# 8x8BulbMatrix.net
KiCad netlist of a schematic drawn in EAGLE
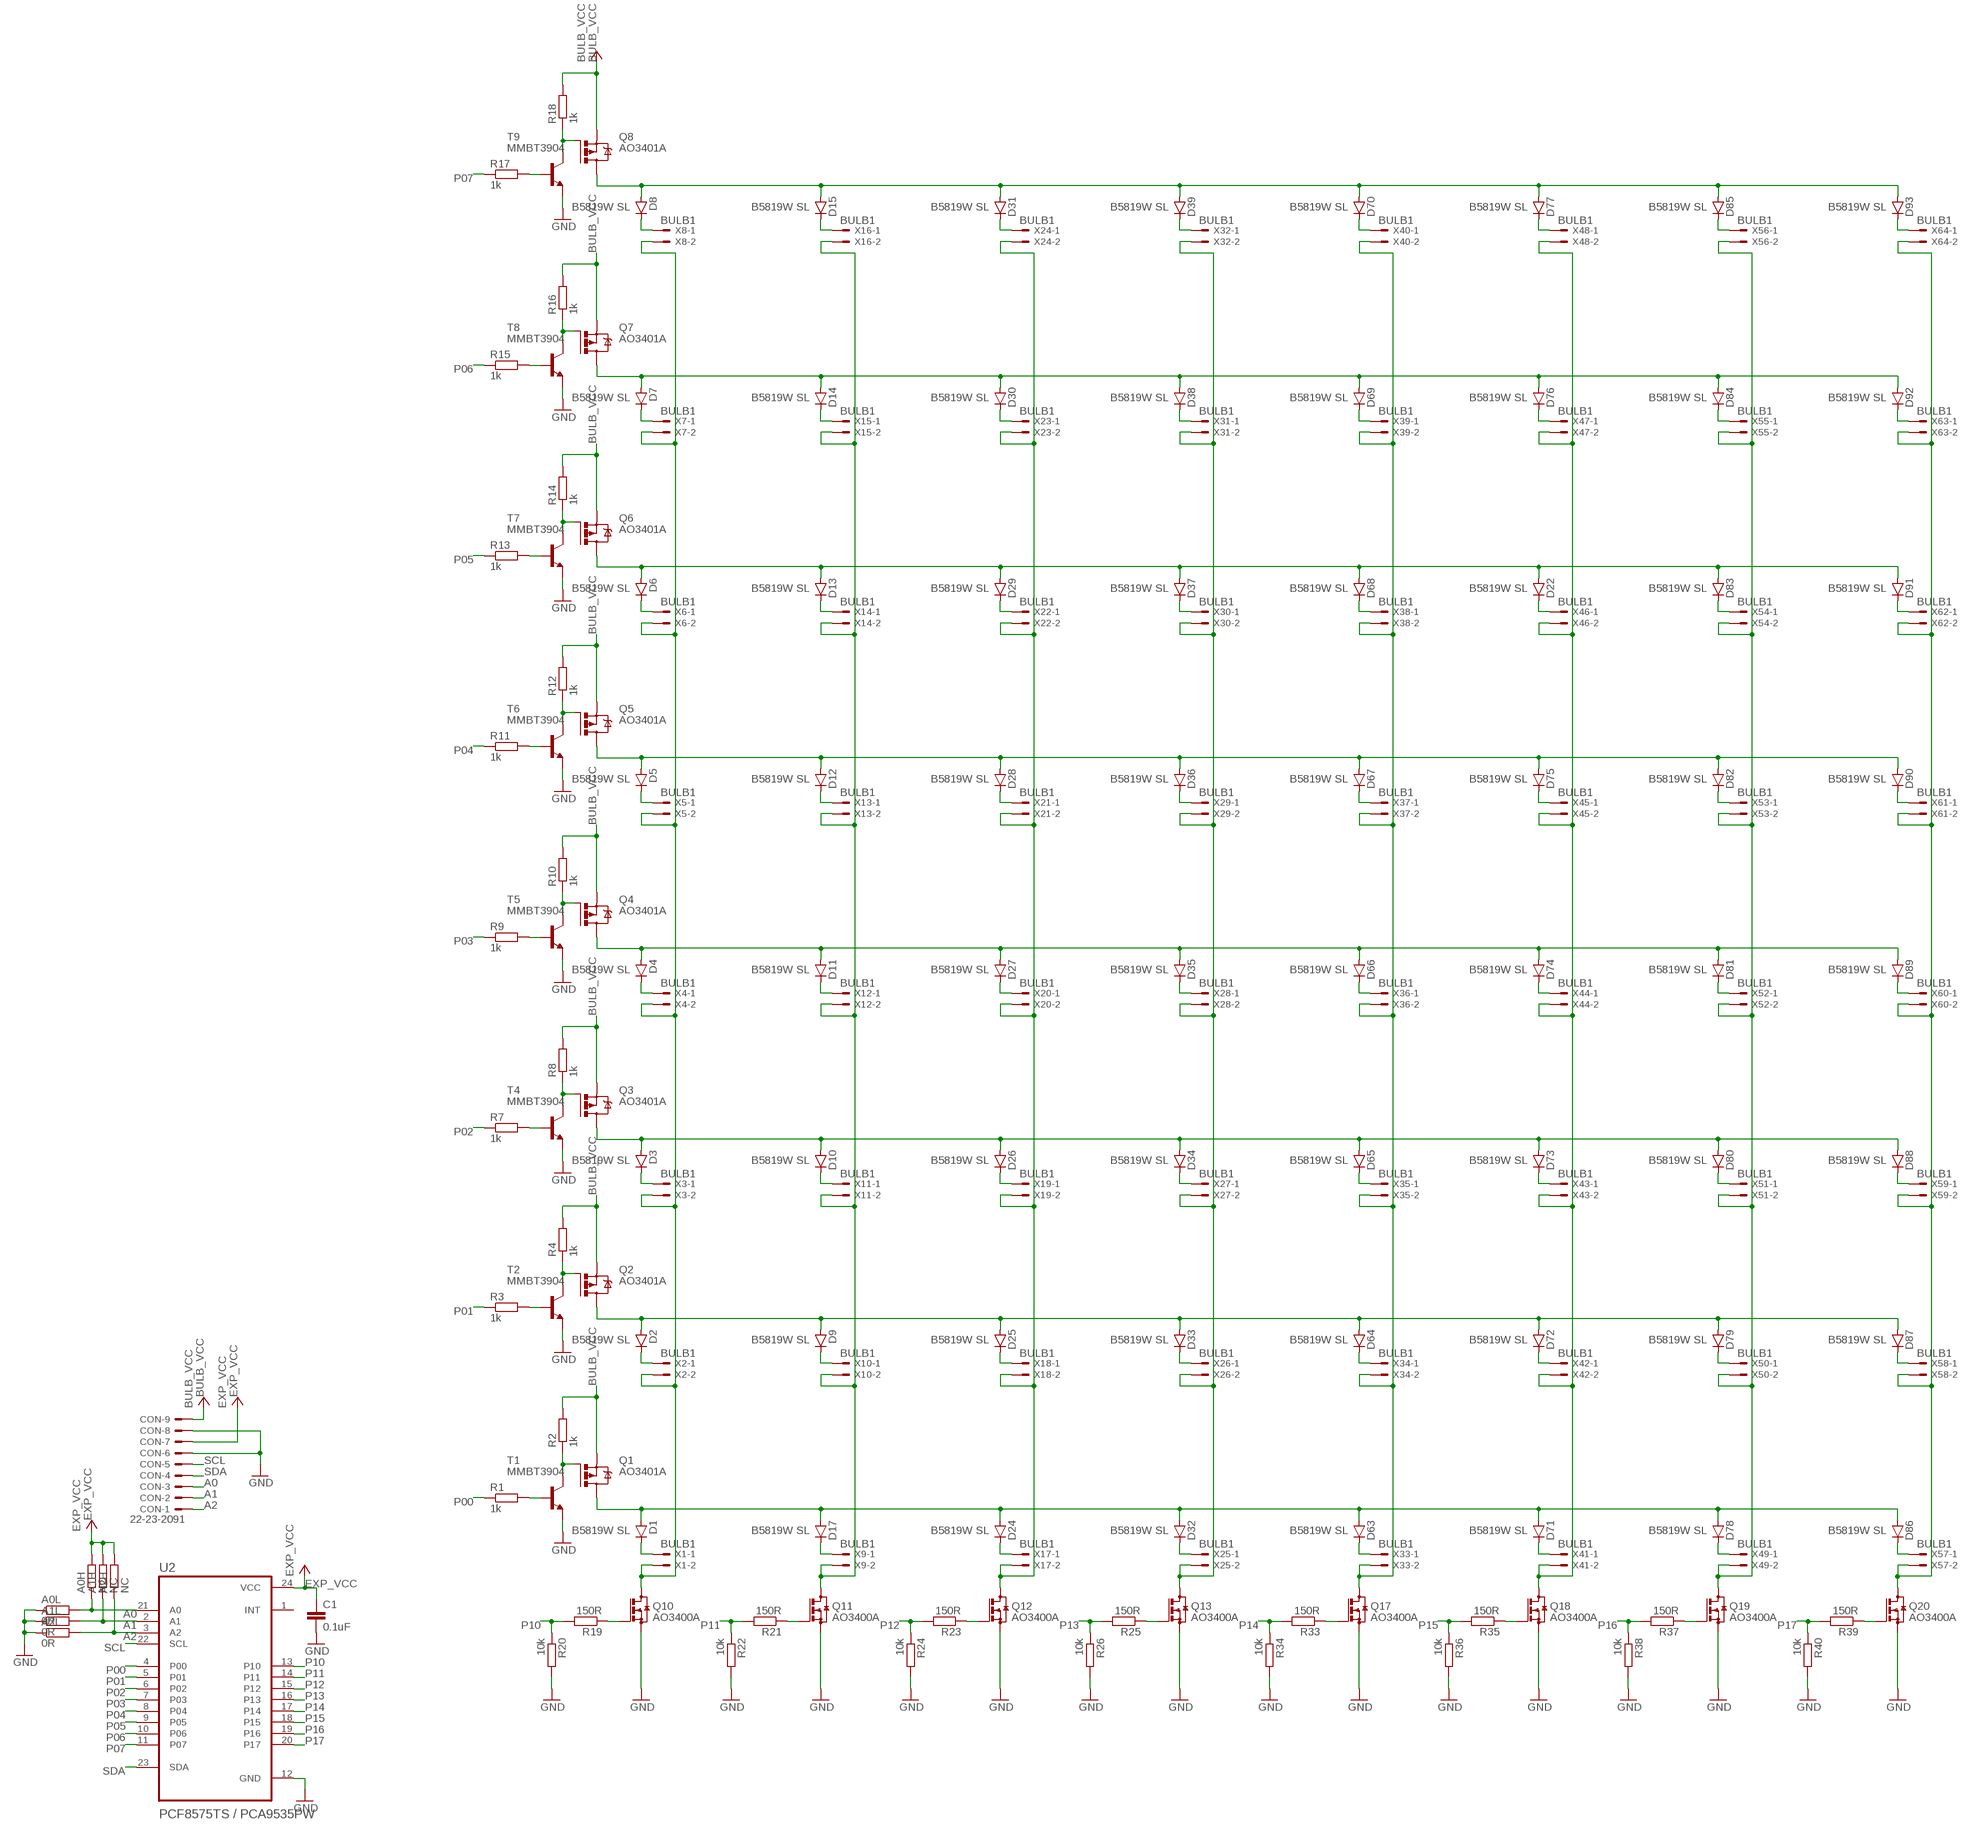
[diagram p0: schematic, sheet 1]

(export (version "E")
  (design (tool "Eeschema 10.0.6"))
  (components
    (comp (ref "A0H")
      (value "NC")
      (footprint "eagle-import:R0603")
      (libsource (lib "eagle-import") (part "R-EU_R0603"))
    )
    (comp (ref "A0L")
      (value "0R")
      (footprint "eagle-import:R0603")
      (libsource (lib "eagle-import") (part "R-EU_R0603"))
    )
    (comp (ref "A1H")
      (value "NC")
      (footprint "eagle-import:R0603")
      (libsource (lib "eagle-import") (part "R-EU_R0603"))
    )
    (comp (ref "A1L")
      (value "0R")
      (footprint "eagle-import:R0603")
      (libsource (lib "eagle-import") (part "R-EU_R0603"))
    )
    (comp (ref "A2H")
      (value "NC")
      (footprint "eagle-import:R0603")
      (libsource (lib "eagle-import") (part "R-EU_R0603"))
    )
    (comp (ref "A2L")
      (value "0R")
      (footprint "eagle-import:R0603")
      (libsource (lib "eagle-import") (part "R-EU_R0603"))
    )
    (comp (ref "C1")
      (value "0.1uF")
      (footprint "eagle-import:C0805")
      (libsource (lib "eagle-import") (part "C-EUC0805"))
    )
    (comp (ref "CON")
      (value "22-23-2091")
      (footprint "eagle-import:22-23-2091")
      (fields (field (name "MF") "MOLEX"))
      (libsource (lib "eagle-import") (part "22-23-2091"))
    )
    (comp (ref "D1")
      (value "B5819W SL")
      (footprint "eagle-import:SOD123")
      (libsource (lib "eagle-import") (part "D-SOD123"))
    )
    (comp (ref "D2")
      (value "B5819W SL")
      (footprint "eagle-import:SOD123")
      (libsource (lib "eagle-import") (part "D-SOD123"))
    )
    (comp (ref "D3")
      (value "B5819W SL")
      (footprint "eagle-import:SOD123")
      (libsource (lib "eagle-import") (part "D-SOD123"))
    )
    (comp (ref "D4")
      (value "B5819W SL")
      (footprint "eagle-import:SOD123")
      (libsource (lib "eagle-import") (part "D-SOD123"))
    )
    (comp (ref "D5")
      (value "B5819W SL")
      (footprint "eagle-import:SOD123")
      (libsource (lib "eagle-import") (part "D-SOD123"))
    )
    (comp (ref "D6")
      (value "B5819W SL")
      (footprint "eagle-import:SOD123")
      (libsource (lib "eagle-import") (part "D-SOD123"))
    )
    (comp (ref "D7")
      (value "B5819W SL")
      (footprint "eagle-import:SOD123")
      (libsource (lib "eagle-import") (part "D-SOD123"))
    )
    (comp (ref "D8")
      (value "B5819W SL")
      (footprint "eagle-import:SOD123")
      (libsource (lib "eagle-import") (part "D-SOD123"))
    )
    (comp (ref "D9")
      (value "B5819W SL")
      (footprint "eagle-import:SOD123")
      (libsource (lib "eagle-import") (part "D-SOD123"))
    )
    (comp (ref "D10")
      (value "B5819W SL")
      (footprint "eagle-import:SOD123")
      (libsource (lib "eagle-import") (part "D-SOD123"))
    )
    (comp (ref "D11")
      (value "B5819W SL")
      (footprint "eagle-import:SOD123")
      (libsource (lib "eagle-import") (part "D-SOD123"))
    )
    (comp (ref "D12")
      (value "B5819W SL")
      (footprint "eagle-import:SOD123")
      (libsource (lib "eagle-import") (part "D-SOD123"))
    )
    (comp (ref "D13")
      (value "B5819W SL")
      (footprint "eagle-import:SOD123")
      (libsource (lib "eagle-import") (part "D-SOD123"))
    )
    (comp (ref "D14")
      (value "B5819W SL")
      (footprint "eagle-import:SOD123")
      (libsource (lib "eagle-import") (part "D-SOD123"))
    )
    (comp (ref "D15")
      (value "B5819W SL")
      (footprint "eagle-import:SOD123")
      (libsource (lib "eagle-import") (part "D-SOD123"))
    )
    (comp (ref "D17")
      (value "B5819W SL")
      (footprint "eagle-import:SOD123")
      (libsource (lib "eagle-import") (part "D-SOD123"))
    )
    (comp (ref "D22")
      (value "B5819W SL")
      (footprint "eagle-import:SOD123")
      (libsource (lib "eagle-import") (part "D-SOD123"))
    )
    (comp (ref "D24")
      (value "B5819W SL")
      (footprint "eagle-import:SOD123")
      (libsource (lib "eagle-import") (part "D-SOD123"))
    )
    (comp (ref "D25")
      (value "B5819W SL")
      (footprint "eagle-import:SOD123")
      (libsource (lib "eagle-import") (part "D-SOD123"))
    )
    (comp (ref "D26")
      (value "B5819W SL")
      (footprint "eagle-import:SOD123")
      (libsource (lib "eagle-import") (part "D-SOD123"))
    )
    (comp (ref "D27")
      (value "B5819W SL")
      (footprint "eagle-import:SOD123")
      (libsource (lib "eagle-import") (part "D-SOD123"))
    )
    (comp (ref "D28")
      (value "B5819W SL")
      (footprint "eagle-import:SOD123")
      (libsource (lib "eagle-import") (part "D-SOD123"))
    )
    (comp (ref "D29")
      (value "B5819W SL")
      (footprint "eagle-import:SOD123")
      (libsource (lib "eagle-import") (part "D-SOD123"))
    )
    (comp (ref "D30")
      (value "B5819W SL")
      (footprint "eagle-import:SOD123")
      (libsource (lib "eagle-import") (part "D-SOD123"))
    )
    (comp (ref "D31")
      (value "B5819W SL")
      (footprint "eagle-import:SOD123")
      (libsource (lib "eagle-import") (part "D-SOD123"))
    )
    (comp (ref "D32")
      (value "B5819W SL")
      (footprint "eagle-import:SOD123")
      (libsource (lib "eagle-import") (part "D-SOD123"))
    )
    (comp (ref "D33")
      (value "B5819W SL")
      (footprint "eagle-import:SOD123")
      (libsource (lib "eagle-import") (part "D-SOD123"))
    )
    (comp (ref "D34")
      (value "B5819W SL")
      (footprint "eagle-import:SOD123")
      (libsource (lib "eagle-import") (part "D-SOD123"))
    )
    (comp (ref "D35")
      (value "B5819W SL")
      (footprint "eagle-import:SOD123")
      (libsource (lib "eagle-import") (part "D-SOD123"))
    )
    (comp (ref "D36")
      (value "B5819W SL")
      (footprint "eagle-import:SOD123")
      (libsource (lib "eagle-import") (part "D-SOD123"))
    )
    (comp (ref "D37")
      (value "B5819W SL")
      (footprint "eagle-import:SOD123")
      (libsource (lib "eagle-import") (part "D-SOD123"))
    )
    (comp (ref "D38")
      (value "B5819W SL")
      (footprint "eagle-import:SOD123")
      (libsource (lib "eagle-import") (part "D-SOD123"))
    )
    (comp (ref "D39")
      (value "B5819W SL")
      (footprint "eagle-import:SOD123")
      (libsource (lib "eagle-import") (part "D-SOD123"))
    )
    (comp (ref "D63")
      (value "B5819W SL")
      (footprint "eagle-import:SOD123")
      (libsource (lib "eagle-import") (part "D-SOD123"))
    )
    (comp (ref "D64")
      (value "B5819W SL")
      (footprint "eagle-import:SOD123")
      (libsource (lib "eagle-import") (part "D-SOD123"))
    )
    (comp (ref "D65")
      (value "B5819W SL")
      (footprint "eagle-import:SOD123")
      (libsource (lib "eagle-import") (part "D-SOD123"))
    )
    (comp (ref "D66")
      (value "B5819W SL")
      (footprint "eagle-import:SOD123")
      (libsource (lib "eagle-import") (part "D-SOD123"))
    )
    (comp (ref "D67")
      (value "B5819W SL")
      (footprint "eagle-import:SOD123")
      (libsource (lib "eagle-import") (part "D-SOD123"))
    )
    (comp (ref "D68")
      (value "B5819W SL")
      (footprint "eagle-import:SOD123")
      (libsource (lib "eagle-import") (part "D-SOD123"))
    )
    (comp (ref "D69")
      (value "B5819W SL")
      (footprint "eagle-import:SOD123")
      (libsource (lib "eagle-import") (part "D-SOD123"))
    )
    (comp (ref "D70")
      (value "B5819W SL")
      (footprint "eagle-import:SOD123")
      (libsource (lib "eagle-import") (part "D-SOD123"))
    )
    (comp (ref "D71")
      (value "B5819W SL")
      (footprint "eagle-import:SOD123")
      (libsource (lib "eagle-import") (part "D-SOD123"))
    )
    (comp (ref "D72")
      (value "B5819W SL")
      (footprint "eagle-import:SOD123")
      (libsource (lib "eagle-import") (part "D-SOD123"))
    )
    (comp (ref "D73")
      (value "B5819W SL")
      (footprint "eagle-import:SOD123")
      (libsource (lib "eagle-import") (part "D-SOD123"))
    )
    (comp (ref "D74")
      (value "B5819W SL")
      (footprint "eagle-import:SOD123")
      (libsource (lib "eagle-import") (part "D-SOD123"))
    )
    (comp (ref "D75")
      (value "B5819W SL")
      (footprint "eagle-import:SOD123")
      (libsource (lib "eagle-import") (part "D-SOD123"))
    )
    (comp (ref "D76")
      (value "B5819W SL")
      (footprint "eagle-import:SOD123")
      (libsource (lib "eagle-import") (part "D-SOD123"))
    )
    (comp (ref "D77")
      (value "B5819W SL")
      (footprint "eagle-import:SOD123")
      (libsource (lib "eagle-import") (part "D-SOD123"))
    )
    (comp (ref "D78")
      (value "B5819W SL")
      (footprint "eagle-import:SOD123")
      (libsource (lib "eagle-import") (part "D-SOD123"))
    )
    (comp (ref "D79")
      (value "B5819W SL")
      (footprint "eagle-import:SOD123")
      (libsource (lib "eagle-import") (part "D-SOD123"))
    )
    (comp (ref "D80")
      (value "B5819W SL")
      (footprint "eagle-import:SOD123")
      (libsource (lib "eagle-import") (part "D-SOD123"))
    )
    (comp (ref "D81")
      (value "B5819W SL")
      (footprint "eagle-import:SOD123")
      (libsource (lib "eagle-import") (part "D-SOD123"))
    )
    (comp (ref "D82")
      (value "B5819W SL")
      (footprint "eagle-import:SOD123")
      (libsource (lib "eagle-import") (part "D-SOD123"))
    )
    (comp (ref "D83")
      (value "B5819W SL")
      (footprint "eagle-import:SOD123")
      (libsource (lib "eagle-import") (part "D-SOD123"))
    )
    (comp (ref "D84")
      (value "B5819W SL")
      (footprint "eagle-import:SOD123")
      (libsource (lib "eagle-import") (part "D-SOD123"))
    )
    (comp (ref "D85")
      (value "B5819W SL")
      (footprint "eagle-import:SOD123")
      (libsource (lib "eagle-import") (part "D-SOD123"))
    )
    (comp (ref "D86")
      (value "B5819W SL")
      (footprint "eagle-import:SOD123")
      (libsource (lib "eagle-import") (part "D-SOD123"))
    )
    (comp (ref "D87")
      (value "B5819W SL")
      (footprint "eagle-import:SOD123")
      (libsource (lib "eagle-import") (part "D-SOD123"))
    )
    (comp (ref "D88")
      (value "B5819W SL")
      (footprint "eagle-import:SOD123")
      (libsource (lib "eagle-import") (part "D-SOD123"))
    )
    (comp (ref "D89")
      (value "B5819W SL")
      (footprint "eagle-import:SOD123")
      (libsource (lib "eagle-import") (part "D-SOD123"))
    )
    (comp (ref "D90")
      (value "B5819W SL")
      (footprint "eagle-import:SOD123")
      (libsource (lib "eagle-import") (part "D-SOD123"))
    )
    (comp (ref "D91")
      (value "B5819W SL")
      (footprint "eagle-import:SOD123")
      (libsource (lib "eagle-import") (part "D-SOD123"))
    )
    (comp (ref "D92")
      (value "B5819W SL")
      (footprint "eagle-import:SOD123")
      (libsource (lib "eagle-import") (part "D-SOD123"))
    )
    (comp (ref "D93")
      (value "B5819W SL")
      (footprint "eagle-import:SOD123")
      (libsource (lib "eagle-import") (part "D-SOD123"))
    )
    (comp (ref "Q1")
      (value "AO3401A")
      (footprint "eagle-import:MICRO3")
      (libsource (lib "eagle-import") (part "IRLML5203"))
    )
    (comp (ref "Q2")
      (value "AO3401A")
      (footprint "eagle-import:MICRO3")
      (libsource (lib "eagle-import") (part "IRLML5203"))
    )
    (comp (ref "Q3")
      (value "AO3401A")
      (footprint "eagle-import:MICRO3")
      (libsource (lib "eagle-import") (part "IRLML5203"))
    )
    (comp (ref "Q4")
      (value "AO3401A")
      (footprint "eagle-import:MICRO3")
      (libsource (lib "eagle-import") (part "IRLML5203"))
    )
    (comp (ref "Q5")
      (value "AO3401A")
      (footprint "eagle-import:MICRO3")
      (libsource (lib "eagle-import") (part "IRLML5203"))
    )
    (comp (ref "Q6")
      (value "AO3401A")
      (footprint "eagle-import:MICRO3")
      (libsource (lib "eagle-import") (part "IRLML5203"))
    )
    (comp (ref "Q7")
      (value "AO3401A")
      (footprint "eagle-import:MICRO3")
      (libsource (lib "eagle-import") (part "IRLML5203"))
    )
    (comp (ref "Q8")
      (value "AO3401A")
      (footprint "eagle-import:MICRO3")
      (libsource (lib "eagle-import") (part "IRLML5203"))
    )
    (comp (ref "Q10")
      (value "AO3400A")
      (footprint "eagle-import:SOT23")
      (libsource (lib "eagle-import") (part "BSS123"))
    )
    (comp (ref "Q11")
      (value "AO3400A")
      (footprint "eagle-import:SOT23")
      (libsource (lib "eagle-import") (part "BSS123"))
    )
    (comp (ref "Q12")
      (value "AO3400A")
      (footprint "eagle-import:SOT23")
      (libsource (lib "eagle-import") (part "BSS123"))
    )
    (comp (ref "Q13")
      (value "AO3400A")
      (footprint "eagle-import:SOT23")
      (libsource (lib "eagle-import") (part "BSS123"))
    )
    (comp (ref "Q17")
      (value "AO3400A")
      (footprint "eagle-import:SOT23")
      (libsource (lib "eagle-import") (part "BSS123"))
    )
    (comp (ref "Q18")
      (value "AO3400A")
      (footprint "eagle-import:SOT23")
      (libsource (lib "eagle-import") (part "BSS123"))
    )
    (comp (ref "Q19")
      (value "AO3400A")
      (footprint "eagle-import:SOT23")
      (libsource (lib "eagle-import") (part "BSS123"))
    )
    (comp (ref "Q20")
      (value "AO3400A")
      (footprint "eagle-import:SOT23")
      (libsource (lib "eagle-import") (part "BSS123"))
    )
    (comp (ref "R1")
      (value "1k")
      (footprint "eagle-import:R0603")
      (libsource (lib "eagle-import") (part "R-EU_R0603"))
    )
    (comp (ref "R2")
      (value "1k")
      (footprint "eagle-import:R0603")
      (libsource (lib "eagle-import") (part "R-EU_R0603"))
    )
    (comp (ref "R3")
      (value "1k")
      (footprint "eagle-import:R0603")
      (libsource (lib "eagle-import") (part "R-EU_R0603"))
    )
    (comp (ref "R4")
      (value "1k")
      (footprint "eagle-import:R0603")
      (libsource (lib "eagle-import") (part "R-EU_R0603"))
    )
    (comp (ref "R7")
      (value "1k")
      (footprint "eagle-import:R0603")
      (libsource (lib "eagle-import") (part "R-EU_R0603"))
    )
    (comp (ref "R8")
      (value "1k")
      (footprint "eagle-import:R0603")
      (libsource (lib "eagle-import") (part "R-EU_R0603"))
    )
    (comp (ref "R9")
      (value "1k")
      (footprint "eagle-import:R0603")
      (libsource (lib "eagle-import") (part "R-EU_R0603"))
    )
    (comp (ref "R10")
      (value "1k")
      (footprint "eagle-import:R0603")
      (libsource (lib "eagle-import") (part "R-EU_R0603"))
    )
    (comp (ref "R11")
      (value "1k")
      (footprint "eagle-import:R0603")
      (libsource (lib "eagle-import") (part "R-EU_R0603"))
    )
    (comp (ref "R12")
      (value "1k")
      (footprint "eagle-import:R0603")
      (libsource (lib "eagle-import") (part "R-EU_R0603"))
    )
    (comp (ref "R13")
      (value "1k")
      (footprint "eagle-import:R0603")
      (libsource (lib "eagle-import") (part "R-EU_R0603"))
    )
    (comp (ref "R14")
      (value "1k")
      (footprint "eagle-import:R0603")
      (libsource (lib "eagle-import") (part "R-EU_R0603"))
    )
    (comp (ref "R15")
      (value "1k")
      (footprint "eagle-import:R0603")
      (libsource (lib "eagle-import") (part "R-EU_R0603"))
    )
    (comp (ref "R16")
      (value "1k")
      (footprint "eagle-import:R0603")
      (libsource (lib "eagle-import") (part "R-EU_R0603"))
    )
    (comp (ref "R17")
      (value "1k")
      (footprint "eagle-import:R0603")
      (libsource (lib "eagle-import") (part "R-EU_R0603"))
    )
    (comp (ref "R18")
      (value "1k")
      (footprint "eagle-import:R0603")
      (libsource (lib "eagle-import") (part "R-EU_R0603"))
    )
    (comp (ref "R19")
      (value "150R")
      (footprint "eagle-import:R0603")
      (libsource (lib "eagle-import") (part "R-EU_R0603"))
    )
    (comp (ref "R20")
      (value "10k")
      (footprint "eagle-import:R0603")
      (libsource (lib "eagle-import") (part "R-EU_R0603"))
    )
    (comp (ref "R21")
      (value "150R")
      (footprint "eagle-import:R0603")
      (libsource (lib "eagle-import") (part "R-EU_R0603"))
    )
    (comp (ref "R22")
      (value "10k")
      (footprint "eagle-import:R0603")
      (libsource (lib "eagle-import") (part "R-EU_R0603"))
    )
    (comp (ref "R23")
      (value "150R")
      (footprint "eagle-import:R0603")
      (libsource (lib "eagle-import") (part "R-EU_R0603"))
    )
    (comp (ref "R24")
      (value "10k")
      (footprint "eagle-import:R0603")
      (libsource (lib "eagle-import") (part "R-EU_R0603"))
    )
    (comp (ref "R25")
      (value "150R")
      (footprint "eagle-import:R0603")
      (libsource (lib "eagle-import") (part "R-EU_R0603"))
    )
    (comp (ref "R26")
      (value "10k")
      (footprint "eagle-import:R0603")
      (libsource (lib "eagle-import") (part "R-EU_R0603"))
    )
    (comp (ref "R33")
      (value "150R")
      (footprint "eagle-import:R0603")
      (libsource (lib "eagle-import") (part "R-EU_R0603"))
    )
    (comp (ref "R34")
      (value "10k")
      (footprint "eagle-import:R0603")
      (libsource (lib "eagle-import") (part "R-EU_R0603"))
    )
    (comp (ref "R35")
      (value "150R")
      (footprint "eagle-import:R0603")
      (libsource (lib "eagle-import") (part "R-EU_R0603"))
    )
    (comp (ref "R36")
      (value "10k")
      (footprint "eagle-import:R0603")
      (libsource (lib "eagle-import") (part "R-EU_R0603"))
    )
    (comp (ref "R37")
      (value "150R")
      (footprint "eagle-import:R0603")
      (libsource (lib "eagle-import") (part "R-EU_R0603"))
    )
    (comp (ref "R38")
      (value "10k")
      (footprint "eagle-import:R0603")
      (libsource (lib "eagle-import") (part "R-EU_R0603"))
    )
    (comp (ref "R39")
      (value "150R")
      (footprint "eagle-import:R0603")
      (libsource (lib "eagle-import") (part "R-EU_R0603"))
    )
    (comp (ref "R40")
      (value "10k")
      (footprint "eagle-import:R0603")
      (libsource (lib "eagle-import") (part "R-EU_R0603"))
    )
    (comp (ref "T1")
      (value "MMBT3904")
      (footprint "eagle-import:SOT23")
      (libsource (lib "eagle-import") (part "BC847"))
    )
    (comp (ref "T2")
      (value "MMBT3904")
      (footprint "eagle-import:SOT23")
      (libsource (lib "eagle-import") (part "BC847"))
    )
    (comp (ref "T4")
      (value "MMBT3904")
      (footprint "eagle-import:SOT23")
      (libsource (lib "eagle-import") (part "BC847"))
    )
    (comp (ref "T5")
      (value "MMBT3904")
      (footprint "eagle-import:SOT23")
      (libsource (lib "eagle-import") (part "BC847"))
    )
    (comp (ref "T6")
      (value "MMBT3904")
      (footprint "eagle-import:SOT23")
      (libsource (lib "eagle-import") (part "BC847"))
    )
    (comp (ref "T7")
      (value "MMBT3904")
      (footprint "eagle-import:SOT23")
      (libsource (lib "eagle-import") (part "BC847"))
    )
    (comp (ref "T8")
      (value "MMBT3904")
      (footprint "eagle-import:SOT23")
      (libsource (lib "eagle-import") (part "BC847"))
    )
    (comp (ref "T9")
      (value "MMBT3904")
      (footprint "eagle-import:SOT23")
      (libsource (lib "eagle-import") (part "BC847"))
    )
    (comp (ref "U2")
      (value "PCF8575TS / PCA9535PW")
      (footprint "eagle-import:SOP65P780X200-24N")
      (fields (field (name "MF") "Texas Instruments") (field (name "MP") "PCF8575DB"))
      (libsource (lib "eagle-import") (part "PCF8575DB"))
    )
    (comp (ref "X1")
      (value "BULB1")
      (footprint "eagle-import:22-23-2021")
      (fields (field (name "MF") "MOLEX") (field (name "MPN") "22-23-2021"))
      (libsource (lib "eagle-import") (part "22-23-2021"))
    )
    (comp (ref "X2")
      (value "BULB1")
      (footprint "eagle-import:22-23-2021")
      (fields (field (name "MF") "MOLEX") (field (name "MPN") "22-23-2021"))
      (libsource (lib "eagle-import") (part "22-23-2021"))
    )
    (comp (ref "X3")
      (value "BULB1")
      (footprint "eagle-import:22-23-2021")
      (fields (field (name "MF") "MOLEX") (field (name "MPN") "22-23-2021"))
      (libsource (lib "eagle-import") (part "22-23-2021"))
    )
    (comp (ref "X4")
      (value "BULB1")
      (footprint "eagle-import:22-23-2021")
      (fields (field (name "MF") "MOLEX") (field (name "MPN") "22-23-2021"))
      (libsource (lib "eagle-import") (part "22-23-2021"))
    )
    (comp (ref "X5")
      (value "BULB1")
      (footprint "eagle-import:22-23-2021")
      (fields (field (name "MF") "MOLEX") (field (name "MPN") "22-23-2021"))
      (libsource (lib "eagle-import") (part "22-23-2021"))
    )
    (comp (ref "X6")
      (value "BULB1")
      (footprint "eagle-import:22-23-2021")
      (fields (field (name "MF") "MOLEX") (field (name "MPN") "22-23-2021"))
      (libsource (lib "eagle-import") (part "22-23-2021"))
    )
    (comp (ref "X7")
      (value "BULB1")
      (footprint "eagle-import:22-23-2021")
      (fields (field (name "MF") "MOLEX") (field (name "MPN") "22-23-2021"))
      (libsource (lib "eagle-import") (part "22-23-2021"))
    )
    (comp (ref "X8")
      (value "BULB1")
      (footprint "eagle-import:22-23-2021")
      (fields (field (name "MF") "MOLEX") (field (name "MPN") "22-23-2021"))
      (libsource (lib "eagle-import") (part "22-23-2021"))
    )
    (comp (ref "X9")
      (value "BULB1")
      (footprint "eagle-import:22-23-2021")
      (fields (field (name "MF") "MOLEX") (field (name "MPN") "22-23-2021"))
      (libsource (lib "eagle-import") (part "22-23-2021"))
    )
    (comp (ref "X10")
      (value "BULB1")
      (footprint "eagle-import:22-23-2021")
      (fields (field (name "MF") "MOLEX") (field (name "MPN") "22-23-2021"))
      (libsource (lib "eagle-import") (part "22-23-2021"))
    )
    (comp (ref "X11")
      (value "BULB1")
      (footprint "eagle-import:22-23-2021")
      (fields (field (name "MF") "MOLEX") (field (name "MPN") "22-23-2021"))
      (libsource (lib "eagle-import") (part "22-23-2021"))
    )
    (comp (ref "X12")
      (value "BULB1")
      (footprint "eagle-import:22-23-2021")
      (fields (field (name "MF") "MOLEX") (field (name "MPN") "22-23-2021"))
      (libsource (lib "eagle-import") (part "22-23-2021"))
    )
    (comp (ref "X13")
      (value "BULB1")
      (footprint "eagle-import:22-23-2021")
      (fields (field (name "MF") "MOLEX") (field (name "MPN") "22-23-2021"))
      (libsource (lib "eagle-import") (part "22-23-2021"))
    )
    (comp (ref "X14")
      (value "BULB1")
      (footprint "eagle-import:22-23-2021")
      (fields (field (name "MF") "MOLEX") (field (name "MPN") "22-23-2021"))
      (libsource (lib "eagle-import") (part "22-23-2021"))
    )
    (comp (ref "X15")
      (value "BULB1")
      (footprint "eagle-import:22-23-2021")
      (fields (field (name "MF") "MOLEX") (field (name "MPN") "22-23-2021"))
      (libsource (lib "eagle-import") (part "22-23-2021"))
    )
    (comp (ref "X16")
      (value "BULB1")
      (footprint "eagle-import:22-23-2021")
      (fields (field (name "MF") "MOLEX") (field (name "MPN") "22-23-2021"))
      (libsource (lib "eagle-import") (part "22-23-2021"))
    )
    (comp (ref "X17")
      (value "BULB1")
      (footprint "eagle-import:22-23-2021")
      (fields (field (name "MF") "MOLEX") (field (name "MPN") "22-23-2021"))
      (libsource (lib "eagle-import") (part "22-23-2021"))
    )
    (comp (ref "X18")
      (value "BULB1")
      (footprint "eagle-import:22-23-2021")
      (fields (field (name "MF") "MOLEX") (field (name "MPN") "22-23-2021"))
      (libsource (lib "eagle-import") (part "22-23-2021"))
    )
    (comp (ref "X19")
      (value "BULB1")
      (footprint "eagle-import:22-23-2021")
      (fields (field (name "MF") "MOLEX") (field (name "MPN") "22-23-2021"))
      (libsource (lib "eagle-import") (part "22-23-2021"))
    )
    (comp (ref "X20")
      (value "BULB1")
      (footprint "eagle-import:22-23-2021")
      (fields (field (name "MF") "MOLEX") (field (name "MPN") "22-23-2021"))
      (libsource (lib "eagle-import") (part "22-23-2021"))
    )
    (comp (ref "X21")
      (value "BULB1")
      (footprint "eagle-import:22-23-2021")
      (fields (field (name "MF") "MOLEX") (field (name "MPN") "22-23-2021"))
      (libsource (lib "eagle-import") (part "22-23-2021"))
    )
    (comp (ref "X22")
      (value "BULB1")
      (footprint "eagle-import:22-23-2021")
      (fields (field (name "MF") "MOLEX") (field (name "MPN") "22-23-2021"))
      (libsource (lib "eagle-import") (part "22-23-2021"))
    )
    (comp (ref "X23")
      (value "BULB1")
      (footprint "eagle-import:22-23-2021")
      (fields (field (name "MF") "MOLEX") (field (name "MPN") "22-23-2021"))
      (libsource (lib "eagle-import") (part "22-23-2021"))
    )
    (comp (ref "X24")
      (value "BULB1")
      (footprint "eagle-import:22-23-2021")
      (fields (field (name "MF") "MOLEX") (field (name "MPN") "22-23-2021"))
      (libsource (lib "eagle-import") (part "22-23-2021"))
    )
    (comp (ref "X25")
      (value "BULB1")
      (footprint "eagle-import:22-23-2021")
      (fields (field (name "MF") "MOLEX") (field (name "MPN") "22-23-2021"))
      (libsource (lib "eagle-import") (part "22-23-2021"))
    )
    (comp (ref "X26")
      (value "BULB1")
      (footprint "eagle-import:22-23-2021")
      (fields (field (name "MF") "MOLEX") (field (name "MPN") "22-23-2021"))
      (libsource (lib "eagle-import") (part "22-23-2021"))
    )
    (comp (ref "X27")
      (value "BULB1")
      (footprint "eagle-import:22-23-2021")
      (fields (field (name "MF") "MOLEX") (field (name "MPN") "22-23-2021"))
      (libsource (lib "eagle-import") (part "22-23-2021"))
    )
    (comp (ref "X28")
      (value "BULB1")
      (footprint "eagle-import:22-23-2021")
      (fields (field (name "MF") "MOLEX") (field (name "MPN") "22-23-2021"))
      (libsource (lib "eagle-import") (part "22-23-2021"))
    )
    (comp (ref "X29")
      (value "BULB1")
      (footprint "eagle-import:22-23-2021")
      (fields (field (name "MF") "MOLEX") (field (name "MPN") "22-23-2021"))
      (libsource (lib "eagle-import") (part "22-23-2021"))
    )
    (comp (ref "X30")
      (value "BULB1")
      (footprint "eagle-import:22-23-2021")
      (fields (field (name "MF") "MOLEX") (field (name "MPN") "22-23-2021"))
      (libsource (lib "eagle-import") (part "22-23-2021"))
    )
    (comp (ref "X31")
      (value "BULB1")
      (footprint "eagle-import:22-23-2021")
      (fields (field (name "MF") "MOLEX") (field (name "MPN") "22-23-2021"))
      (libsource (lib "eagle-import") (part "22-23-2021"))
    )
    (comp (ref "X32")
      (value "BULB1")
      (footprint "eagle-import:22-23-2021")
      (fields (field (name "MF") "MOLEX") (field (name "MPN") "22-23-2021"))
      (libsource (lib "eagle-import") (part "22-23-2021"))
    )
    (comp (ref "X33")
      (value "BULB1")
      (footprint "eagle-import:22-23-2021")
      (fields (field (name "MF") "MOLEX") (field (name "MPN") "22-23-2021"))
      (libsource (lib "eagle-import") (part "22-23-2021"))
    )
    (comp (ref "X34")
      (value "BULB1")
      (footprint "eagle-import:22-23-2021")
      (fields (field (name "MF") "MOLEX") (field (name "MPN") "22-23-2021"))
      (libsource (lib "eagle-import") (part "22-23-2021"))
    )
    (comp (ref "X35")
      (value "BULB1")
      (footprint "eagle-import:22-23-2021")
      (fields (field (name "MF") "MOLEX") (field (name "MPN") "22-23-2021"))
      (libsource (lib "eagle-import") (part "22-23-2021"))
    )
    (comp (ref "X36")
      (value "BULB1")
      (footprint "eagle-import:22-23-2021")
      (fields (field (name "MF") "MOLEX") (field (name "MPN") "22-23-2021"))
      (libsource (lib "eagle-import") (part "22-23-2021"))
    )
    (comp (ref "X37")
      (value "BULB1")
      (footprint "eagle-import:22-23-2021")
      (fields (field (name "MF") "MOLEX") (field (name "MPN") "22-23-2021"))
      (libsource (lib "eagle-import") (part "22-23-2021"))
    )
    (comp (ref "X38")
      (value "BULB1")
      (footprint "eagle-import:22-23-2021")
      (fields (field (name "MF") "MOLEX") (field (name "MPN") "22-23-2021"))
      (libsource (lib "eagle-import") (part "22-23-2021"))
    )
    (comp (ref "X39")
      (value "BULB1")
      (footprint "eagle-import:22-23-2021")
      (fields (field (name "MF") "MOLEX") (field (name "MPN") "22-23-2021"))
      (libsource (lib "eagle-import") (part "22-23-2021"))
    )
    (comp (ref "X40")
      (value "BULB1")
      (footprint "eagle-import:22-23-2021")
      (fields (field (name "MF") "MOLEX") (field (name "MPN") "22-23-2021"))
      (libsource (lib "eagle-import") (part "22-23-2021"))
    )
    (comp (ref "X41")
      (value "BULB1")
      (footprint "eagle-import:22-23-2021")
      (fields (field (name "MF") "MOLEX") (field (name "MPN") "22-23-2021"))
      (libsource (lib "eagle-import") (part "22-23-2021"))
    )
    (comp (ref "X42")
      (value "BULB1")
      (footprint "eagle-import:22-23-2021")
      (fields (field (name "MF") "MOLEX") (field (name "MPN") "22-23-2021"))
      (libsource (lib "eagle-import") (part "22-23-2021"))
    )
    (comp (ref "X43")
      (value "BULB1")
      (footprint "eagle-import:22-23-2021")
      (fields (field (name "MF") "MOLEX") (field (name "MPN") "22-23-2021"))
      (libsource (lib "eagle-import") (part "22-23-2021"))
    )
    (comp (ref "X44")
      (value "BULB1")
      (footprint "eagle-import:22-23-2021")
      (fields (field (name "MF") "MOLEX") (field (name "MPN") "22-23-2021"))
      (libsource (lib "eagle-import") (part "22-23-2021"))
    )
    (comp (ref "X45")
      (value "BULB1")
      (footprint "eagle-import:22-23-2021")
      (fields (field (name "MF") "MOLEX") (field (name "MPN") "22-23-2021"))
      (libsource (lib "eagle-import") (part "22-23-2021"))
    )
    (comp (ref "X46")
      (value "BULB1")
      (footprint "eagle-import:22-23-2021")
      (fields (field (name "MF") "MOLEX") (field (name "MPN") "22-23-2021"))
      (libsource (lib "eagle-import") (part "22-23-2021"))
    )
    (comp (ref "X47")
      (value "BULB1")
      (footprint "eagle-import:22-23-2021")
      (fields (field (name "MF") "MOLEX") (field (name "MPN") "22-23-2021"))
      (libsource (lib "eagle-import") (part "22-23-2021"))
    )
    (comp (ref "X48")
      (value "BULB1")
      (footprint "eagle-import:22-23-2021")
      (fields (field (name "MF") "MOLEX") (field (name "MPN") "22-23-2021"))
      (libsource (lib "eagle-import") (part "22-23-2021"))
    )
    (comp (ref "X49")
      (value "BULB1")
      (footprint "eagle-import:22-23-2021")
      (fields (field (name "MF") "MOLEX") (field (name "MPN") "22-23-2021"))
      (libsource (lib "eagle-import") (part "22-23-2021"))
    )
    (comp (ref "X50")
      (value "BULB1")
      (footprint "eagle-import:22-23-2021")
      (fields (field (name "MF") "MOLEX") (field (name "MPN") "22-23-2021"))
      (libsource (lib "eagle-import") (part "22-23-2021"))
    )
    (comp (ref "X51")
      (value "BULB1")
      (footprint "eagle-import:22-23-2021")
      (fields (field (name "MF") "MOLEX") (field (name "MPN") "22-23-2021"))
      (libsource (lib "eagle-import") (part "22-23-2021"))
    )
    (comp (ref "X52")
      (value "BULB1")
      (footprint "eagle-import:22-23-2021")
      (fields (field (name "MF") "MOLEX") (field (name "MPN") "22-23-2021"))
      (libsource (lib "eagle-import") (part "22-23-2021"))
    )
    (comp (ref "X53")
      (value "BULB1")
      (footprint "eagle-import:22-23-2021")
      (fields (field (name "MF") "MOLEX") (field (name "MPN") "22-23-2021"))
      (libsource (lib "eagle-import") (part "22-23-2021"))
    )
    (comp (ref "X54")
      (value "BULB1")
      (footprint "eagle-import:22-23-2021")
      (fields (field (name "MF") "MOLEX") (field (name "MPN") "22-23-2021"))
      (libsource (lib "eagle-import") (part "22-23-2021"))
    )
    (comp (ref "X55")
      (value "BULB1")
      (footprint "eagle-import:22-23-2021")
      (fields (field (name "MF") "MOLEX") (field (name "MPN") "22-23-2021"))
      (libsource (lib "eagle-import") (part "22-23-2021"))
    )
    (comp (ref "X56")
      (value "BULB1")
      (footprint "eagle-import:22-23-2021")
      (fields (field (name "MF") "MOLEX") (field (name "MPN") "22-23-2021"))
      (libsource (lib "eagle-import") (part "22-23-2021"))
    )
    (comp (ref "X57")
      (value "BULB1")
      (footprint "eagle-import:22-23-2021")
      (fields (field (name "MF") "MOLEX") (field (name "MPN") "22-23-2021"))
      (libsource (lib "eagle-import") (part "22-23-2021"))
    )
    (comp (ref "X58")
      (value "BULB1")
      (footprint "eagle-import:22-23-2021")
      (fields (field (name "MF") "MOLEX") (field (name "MPN") "22-23-2021"))
      (libsource (lib "eagle-import") (part "22-23-2021"))
    )
    (comp (ref "X59")
      (value "BULB1")
      (footprint "eagle-import:22-23-2021")
      (fields (field (name "MF") "MOLEX") (field (name "MPN") "22-23-2021"))
      (libsource (lib "eagle-import") (part "22-23-2021"))
    )
    (comp (ref "X60")
      (value "BULB1")
      (footprint "eagle-import:22-23-2021")
      (fields (field (name "MF") "MOLEX") (field (name "MPN") "22-23-2021"))
      (libsource (lib "eagle-import") (part "22-23-2021"))
    )
    (comp (ref "X61")
      (value "BULB1")
      (footprint "eagle-import:22-23-2021")
      (fields (field (name "MF") "MOLEX") (field (name "MPN") "22-23-2021"))
      (libsource (lib "eagle-import") (part "22-23-2021"))
    )
    (comp (ref "X62")
      (value "BULB1")
      (footprint "eagle-import:22-23-2021")
      (fields (field (name "MF") "MOLEX") (field (name "MPN") "22-23-2021"))
      (libsource (lib "eagle-import") (part "22-23-2021"))
    )
    (comp (ref "X63")
      (value "BULB1")
      (footprint "eagle-import:22-23-2021")
      (fields (field (name "MF") "MOLEX") (field (name "MPN") "22-23-2021"))
      (libsource (lib "eagle-import") (part "22-23-2021"))
    )
    (comp (ref "X64")
      (value "BULB1")
      (footprint "eagle-import:22-23-2021")
      (fields (field (name "MF") "MOLEX") (field (name "MPN") "22-23-2021"))
      (libsource (lib "eagle-import") (part "22-23-2021"))
    )
  )
  (nets
    (net (code "1") (name "/A0") (class "Default")
      (node (ref "A0H") (pin "1") (pinfunction "1_1") (pintype "passive"))
      (node (ref "A0L") (pin "2") (pinfunction "2_2") (pintype "passive"))
      (node (ref "CON") (pin "3") (pinfunction "S_3") (pintype "passive"))
      (node (ref "U2") (pin "21") (pinfunction "A0_21") (pintype "input"))
    )
    (net (code "2") (name "/A1") (class "Default")
      (node (ref "A1H") (pin "1") (pinfunction "1_1") (pintype "passive"))
      (node (ref "A1L") (pin "2") (pinfunction "2_2") (pintype "passive"))
      (node (ref "CON") (pin "2") (pinfunction "S_2") (pintype "passive"))
      (node (ref "U2") (pin "2") (pinfunction "A1_2") (pintype "input"))
    )
    (net (code "3") (name "/A2") (class "Default")
      (node (ref "A2H") (pin "1") (pinfunction "1_1") (pintype "passive"))
      (node (ref "A2L") (pin "2") (pinfunction "2_2") (pintype "passive"))
      (node (ref "CON") (pin "1") (pinfunction "S_1") (pintype "passive"))
      (node (ref "U2") (pin "3") (pinfunction "A2_3") (pintype "input"))
    )
    (net (code "4") (name "/P00") (class "Default")
      (node (ref "R1") (pin "1") (pinfunction "1_1") (pintype "passive"))
      (node (ref "U2") (pin "4") (pinfunction "P00_4") (pintype "bidirectional"))
    )
    (net (code "5") (name "/P01") (class "Default")
      (node (ref "R3") (pin "1") (pinfunction "1_1") (pintype "passive"))
      (node (ref "U2") (pin "5") (pinfunction "P01_5") (pintype "bidirectional"))
    )
    (net (code "6") (name "/P02") (class "Default")
      (node (ref "R7") (pin "1") (pinfunction "1_1") (pintype "passive"))
      (node (ref "U2") (pin "6") (pinfunction "P02_6") (pintype "bidirectional"))
    )
    (net (code "7") (name "/P03") (class "Default")
      (node (ref "R9") (pin "1") (pinfunction "1_1") (pintype "passive"))
      (node (ref "U2") (pin "7") (pinfunction "P03_7") (pintype "bidirectional"))
    )
    (net (code "8") (name "/P04") (class "Default")
      (node (ref "R11") (pin "1") (pinfunction "1_1") (pintype "passive"))
      (node (ref "U2") (pin "8") (pinfunction "P04_8") (pintype "bidirectional"))
    )
    (net (code "9") (name "/P05") (class "Default")
      (node (ref "R13") (pin "1") (pinfunction "1_1") (pintype "passive"))
      (node (ref "U2") (pin "9") (pinfunction "P05_9") (pintype "bidirectional"))
    )
    (net (code "10") (name "/P06") (class "Default")
      (node (ref "R15") (pin "1") (pinfunction "1_1") (pintype "passive"))
      (node (ref "U2") (pin "10") (pinfunction "P06_10") (pintype "bidirectional"))
    )
    (net (code "11") (name "/P07") (class "Default")
      (node (ref "R17") (pin "1") (pinfunction "1_1") (pintype "passive"))
      (node (ref "U2") (pin "11") (pinfunction "P07_11") (pintype "bidirectional"))
    )
    (net (code "12") (name "/P10") (class "Default")
      (node (ref "R19") (pin "2") (pinfunction "2_2") (pintype "passive"))
      (node (ref "R20") (pin "1") (pinfunction "1_1") (pintype "passive"))
      (node (ref "U2") (pin "13") (pinfunction "P10_13") (pintype "bidirectional"))
    )
    (net (code "13") (name "/P11") (class "Default")
      (node (ref "R21") (pin "2") (pinfunction "2_2") (pintype "passive"))
      (node (ref "R22") (pin "1") (pinfunction "1_1") (pintype "passive"))
      (node (ref "U2") (pin "14") (pinfunction "P11_14") (pintype "bidirectional"))
    )
    (net (code "14") (name "/P12") (class "Default")
      (node (ref "R23") (pin "2") (pinfunction "2_2") (pintype "passive"))
      (node (ref "R24") (pin "1") (pinfunction "1_1") (pintype "passive"))
      (node (ref "U2") (pin "15") (pinfunction "P12_15") (pintype "bidirectional"))
    )
    (net (code "15") (name "/P13") (class "Default")
      (node (ref "R25") (pin "2") (pinfunction "2_2") (pintype "passive"))
      (node (ref "R26") (pin "1") (pinfunction "1_1") (pintype "passive"))
      (node (ref "U2") (pin "16") (pinfunction "P13_16") (pintype "bidirectional"))
    )
    (net (code "16") (name "/P14") (class "Default")
      (node (ref "R33") (pin "2") (pinfunction "2_2") (pintype "passive"))
      (node (ref "R34") (pin "1") (pinfunction "1_1") (pintype "passive"))
      (node (ref "U2") (pin "17") (pinfunction "P14_17") (pintype "bidirectional"))
    )
    (net (code "17") (name "/P15") (class "Default")
      (node (ref "R35") (pin "2") (pinfunction "2_2") (pintype "passive"))
      (node (ref "R36") (pin "1") (pinfunction "1_1") (pintype "passive"))
      (node (ref "U2") (pin "18") (pinfunction "P15_18") (pintype "bidirectional"))
    )
    (net (code "18") (name "/P16") (class "Default")
      (node (ref "R37") (pin "2") (pinfunction "2_2") (pintype "passive"))
      (node (ref "R38") (pin "1") (pinfunction "1_1") (pintype "passive"))
      (node (ref "U2") (pin "19") (pinfunction "P16_19") (pintype "bidirectional"))
    )
    (net (code "19") (name "/P17") (class "Default")
      (node (ref "R39") (pin "2") (pinfunction "2_2") (pintype "passive"))
      (node (ref "R40") (pin "1") (pinfunction "1_1") (pintype "passive"))
      (node (ref "U2") (pin "20") (pinfunction "P17_20") (pintype "bidirectional"))
    )
    (net (code "20") (name "/SCL") (class "Default")
      (node (ref "CON") (pin "5") (pinfunction "S_5") (pintype "passive"))
      (node (ref "U2") (pin "22") (pinfunction "SCL_22") (pintype "input"))
    )
    (net (code "21") (name "/SDA") (class "Default")
      (node (ref "CON") (pin "4") (pinfunction "S_4") (pintype "passive"))
      (node (ref "U2") (pin "23") (pinfunction "SDA_23") (pintype "bidirectional"))
    )
    (net (code "22") (name "BULB_VCC") (class "Default")
      (node (ref "CON") (pin "9") (pinfunction "S_9") (pintype "passive"))
      (node (ref "Q1") (pin "2") (pinfunction "S_2") (pintype "passive"))
      (node (ref "Q2") (pin "2") (pinfunction "S_2") (pintype "passive"))
      (node (ref "Q3") (pin "2") (pinfunction "S_2") (pintype "passive"))
      (node (ref "Q4") (pin "2") (pinfunction "S_2") (pintype "passive"))
      (node (ref "Q5") (pin "2") (pinfunction "S_2") (pintype "passive"))
      (node (ref "Q6") (pin "2") (pinfunction "S_2") (pintype "passive"))
      (node (ref "Q7") (pin "2") (pinfunction "S_2") (pintype "passive"))
      (node (ref "Q8") (pin "2") (pinfunction "S_2") (pintype "passive"))
      (node (ref "R10") (pin "2") (pinfunction "2_2") (pintype "passive"))
      (node (ref "R12") (pin "2") (pinfunction "2_2") (pintype "passive"))
      (node (ref "R14") (pin "2") (pinfunction "2_2") (pintype "passive"))
      (node (ref "R16") (pin "2") (pinfunction "2_2") (pintype "passive"))
      (node (ref "R18") (pin "2") (pinfunction "2_2") (pintype "passive"))
      (node (ref "R2") (pin "2") (pinfunction "2_2") (pintype "passive"))
      (node (ref "R4") (pin "2") (pinfunction "2_2") (pintype "passive"))
      (node (ref "R8") (pin "2") (pinfunction "2_2") (pintype "passive"))
    )
    (net (code "23") (name "EXP_VCC") (class "Default")
      (node (ref "A0H") (pin "2") (pinfunction "2_2") (pintype "passive"))
      (node (ref "A1H") (pin "2") (pinfunction "2_2") (pintype "passive"))
      (node (ref "A2H") (pin "2") (pinfunction "2_2") (pintype "passive"))
      (node (ref "C1") (pin "1") (pinfunction "1_1") (pintype "passive"))
      (node (ref "CON") (pin "7") (pinfunction "S_7") (pintype "passive"))
      (node (ref "U2") (pin "24") (pinfunction "VCC_24") (pintype "power_in"))
    )
    (net (code "24") (name "GND") (class "Default")
      (node (ref "A0L") (pin "1") (pinfunction "1_1") (pintype "passive"))
      (node (ref "A1L") (pin "1") (pinfunction "1_1") (pintype "passive"))
      (node (ref "A2L") (pin "1") (pinfunction "1_1") (pintype "passive"))
      (node (ref "C1") (pin "2") (pinfunction "2_2") (pintype "passive"))
      (node (ref "CON") (pin "6") (pinfunction "S_6") (pintype "passive"))
      (node (ref "CON") (pin "8") (pinfunction "S_8") (pintype "passive"))
      (node (ref "Q10") (pin "2") (pinfunction "S_2") (pintype "passive"))
      (node (ref "Q11") (pin "2") (pinfunction "S_2") (pintype "passive"))
      (node (ref "Q12") (pin "2") (pinfunction "S_2") (pintype "passive"))
      (node (ref "Q13") (pin "2") (pinfunction "S_2") (pintype "passive"))
      (node (ref "Q17") (pin "2") (pinfunction "S_2") (pintype "passive"))
      (node (ref "Q18") (pin "2") (pinfunction "S_2") (pintype "passive"))
      (node (ref "Q19") (pin "2") (pinfunction "S_2") (pintype "passive"))
      (node (ref "Q20") (pin "2") (pinfunction "S_2") (pintype "passive"))
      (node (ref "R20") (pin "2") (pinfunction "2_2") (pintype "passive"))
      (node (ref "R22") (pin "2") (pinfunction "2_2") (pintype "passive"))
      (node (ref "R24") (pin "2") (pinfunction "2_2") (pintype "passive"))
      (node (ref "R26") (pin "2") (pinfunction "2_2") (pintype "passive"))
      (node (ref "R34") (pin "2") (pinfunction "2_2") (pintype "passive"))
      (node (ref "R36") (pin "2") (pinfunction "2_2") (pintype "passive"))
      (node (ref "R38") (pin "2") (pinfunction "2_2") (pintype "passive"))
      (node (ref "R40") (pin "2") (pinfunction "2_2") (pintype "passive"))
      (node (ref "T1") (pin "2") (pinfunction "E_2") (pintype "passive"))
      (node (ref "T2") (pin "2") (pinfunction "E_2") (pintype "passive"))
      (node (ref "T4") (pin "2") (pinfunction "E_2") (pintype "passive"))
      (node (ref "T5") (pin "2") (pinfunction "E_2") (pintype "passive"))
      (node (ref "T6") (pin "2") (pinfunction "E_2") (pintype "passive"))
      (node (ref "T7") (pin "2") (pinfunction "E_2") (pintype "passive"))
      (node (ref "T8") (pin "2") (pinfunction "E_2") (pintype "passive"))
      (node (ref "T9") (pin "2") (pinfunction "E_2") (pintype "passive"))
      (node (ref "U2") (pin "12") (pinfunction "GND_12") (pintype "power_in"))
    )
    (net (code "25") (name "Net-(D1-A)") (class "Default")
      (node (ref "D1") (pin "2") (pinfunction "A_2") (pintype "passive"))
      (node (ref "D17") (pin "2") (pinfunction "A_2") (pintype "passive"))
      (node (ref "D24") (pin "2") (pinfunction "A_2") (pintype "passive"))
      (node (ref "D32") (pin "2") (pinfunction "A_2") (pintype "passive"))
      (node (ref "D63") (pin "2") (pinfunction "A_2") (pintype "passive"))
      (node (ref "D71") (pin "2") (pinfunction "A_2") (pintype "passive"))
      (node (ref "D78") (pin "2") (pinfunction "A_2") (pintype "passive"))
      (node (ref "D86") (pin "2") (pinfunction "A_2") (pintype "passive"))
      (node (ref "Q1") (pin "3") (pinfunction "D_3") (pintype "passive"))
    )
    (net (code "26") (name "Net-(D1-C)") (class "Default")
      (node (ref "D1") (pin "1") (pinfunction "C_1") (pintype "passive"))
      (node (ref "X1") (pin "1") (pinfunction "S_1") (pintype "passive"))
    )
    (net (code "27") (name "Net-(D2-A)") (class "Default")
      (node (ref "D2") (pin "2") (pinfunction "A_2") (pintype "passive"))
      (node (ref "D25") (pin "2") (pinfunction "A_2") (pintype "passive"))
      (node (ref "D33") (pin "2") (pinfunction "A_2") (pintype "passive"))
      (node (ref "D64") (pin "2") (pinfunction "A_2") (pintype "passive"))
      (node (ref "D72") (pin "2") (pinfunction "A_2") (pintype "passive"))
      (node (ref "D79") (pin "2") (pinfunction "A_2") (pintype "passive"))
      (node (ref "D87") (pin "2") (pinfunction "A_2") (pintype "passive"))
      (node (ref "D9") (pin "2") (pinfunction "A_2") (pintype "passive"))
      (node (ref "Q2") (pin "3") (pinfunction "D_3") (pintype "passive"))
    )
    (net (code "28") (name "Net-(D2-C)") (class "Default")
      (node (ref "D2") (pin "1") (pinfunction "C_1") (pintype "passive"))
      (node (ref "X2") (pin "1") (pinfunction "S_1") (pintype "passive"))
    )
    (net (code "29") (name "Net-(D3-C)") (class "Default")
      (node (ref "D3") (pin "1") (pinfunction "C_1") (pintype "passive"))
      (node (ref "X3") (pin "1") (pinfunction "S_1") (pintype "passive"))
    )
    (net (code "30") (name "Net-(D4-C)") (class "Default")
      (node (ref "D4") (pin "1") (pinfunction "C_1") (pintype "passive"))
      (node (ref "X4") (pin "1") (pinfunction "S_1") (pintype "passive"))
    )
    (net (code "31") (name "Net-(D5-C)") (class "Default")
      (node (ref "D5") (pin "1") (pinfunction "C_1") (pintype "passive"))
      (node (ref "X5") (pin "1") (pinfunction "S_1") (pintype "passive"))
    )
    (net (code "32") (name "Net-(D6-C)") (class "Default")
      (node (ref "D6") (pin "1") (pinfunction "C_1") (pintype "passive"))
      (node (ref "X6") (pin "1") (pinfunction "S_1") (pintype "passive"))
    )
    (net (code "33") (name "Net-(D7-C)") (class "Default")
      (node (ref "D7") (pin "1") (pinfunction "C_1") (pintype "passive"))
      (node (ref "X7") (pin "1") (pinfunction "S_1") (pintype "passive"))
    )
    (net (code "34") (name "Net-(D8-C)") (class "Default")
      (node (ref "D8") (pin "1") (pinfunction "C_1") (pintype "passive"))
      (node (ref "X8") (pin "1") (pinfunction "S_1") (pintype "passive"))
    )
    (net (code "35") (name "Net-(D9-C)") (class "Default")
      (node (ref "D9") (pin "1") (pinfunction "C_1") (pintype "passive"))
      (node (ref "X10") (pin "1") (pinfunction "S_1") (pintype "passive"))
    )
    (net (code "36") (name "Net-(D10-A)") (class "Default")
      (node (ref "D10") (pin "2") (pinfunction "A_2") (pintype "passive"))
      (node (ref "D26") (pin "2") (pinfunction "A_2") (pintype "passive"))
      (node (ref "D3") (pin "2") (pinfunction "A_2") (pintype "passive"))
      (node (ref "D34") (pin "2") (pinfunction "A_2") (pintype "passive"))
      (node (ref "D65") (pin "2") (pinfunction "A_2") (pintype "passive"))
      (node (ref "D73") (pin "2") (pinfunction "A_2") (pintype "passive"))
      (node (ref "D80") (pin "2") (pinfunction "A_2") (pintype "passive"))
      (node (ref "D88") (pin "2") (pinfunction "A_2") (pintype "passive"))
      (node (ref "Q3") (pin "3") (pinfunction "D_3") (pintype "passive"))
    )
    (net (code "37") (name "Net-(D10-C)") (class "Default")
      (node (ref "D10") (pin "1") (pinfunction "C_1") (pintype "passive"))
      (node (ref "X11") (pin "1") (pinfunction "S_1") (pintype "passive"))
    )
    (net (code "38") (name "Net-(D11-A)") (class "Default")
      (node (ref "D11") (pin "2") (pinfunction "A_2") (pintype "passive"))
      (node (ref "D27") (pin "2") (pinfunction "A_2") (pintype "passive"))
      (node (ref "D35") (pin "2") (pinfunction "A_2") (pintype "passive"))
      (node (ref "D4") (pin "2") (pinfunction "A_2") (pintype "passive"))
      (node (ref "D66") (pin "2") (pinfunction "A_2") (pintype "passive"))
      (node (ref "D74") (pin "2") (pinfunction "A_2") (pintype "passive"))
      (node (ref "D81") (pin "2") (pinfunction "A_2") (pintype "passive"))
      (node (ref "D89") (pin "2") (pinfunction "A_2") (pintype "passive"))
      (node (ref "Q4") (pin "3") (pinfunction "D_3") (pintype "passive"))
    )
    (net (code "39") (name "Net-(D11-C)") (class "Default")
      (node (ref "D11") (pin "1") (pinfunction "C_1") (pintype "passive"))
      (node (ref "X12") (pin "1") (pinfunction "S_1") (pintype "passive"))
    )
    (net (code "40") (name "Net-(D12-A)") (class "Default")
      (node (ref "D12") (pin "2") (pinfunction "A_2") (pintype "passive"))
      (node (ref "D28") (pin "2") (pinfunction "A_2") (pintype "passive"))
      (node (ref "D36") (pin "2") (pinfunction "A_2") (pintype "passive"))
      (node (ref "D5") (pin "2") (pinfunction "A_2") (pintype "passive"))
      (node (ref "D67") (pin "2") (pinfunction "A_2") (pintype "passive"))
      (node (ref "D75") (pin "2") (pinfunction "A_2") (pintype "passive"))
      (node (ref "D82") (pin "2") (pinfunction "A_2") (pintype "passive"))
      (node (ref "D90") (pin "2") (pinfunction "A_2") (pintype "passive"))
      (node (ref "Q5") (pin "3") (pinfunction "D_3") (pintype "passive"))
    )
    (net (code "41") (name "Net-(D12-C)") (class "Default")
      (node (ref "D12") (pin "1") (pinfunction "C_1") (pintype "passive"))
      (node (ref "X13") (pin "1") (pinfunction "S_1") (pintype "passive"))
    )
    (net (code "42") (name "Net-(D13-A)") (class "Default")
      (node (ref "D13") (pin "2") (pinfunction "A_2") (pintype "passive"))
      (node (ref "D22") (pin "2") (pinfunction "A_2") (pintype "passive"))
      (node (ref "D29") (pin "2") (pinfunction "A_2") (pintype "passive"))
      (node (ref "D37") (pin "2") (pinfunction "A_2") (pintype "passive"))
      (node (ref "D6") (pin "2") (pinfunction "A_2") (pintype "passive"))
      (node (ref "D68") (pin "2") (pinfunction "A_2") (pintype "passive"))
      (node (ref "D83") (pin "2") (pinfunction "A_2") (pintype "passive"))
      (node (ref "D91") (pin "2") (pinfunction "A_2") (pintype "passive"))
      (node (ref "Q6") (pin "3") (pinfunction "D_3") (pintype "passive"))
    )
    (net (code "43") (name "Net-(D13-C)") (class "Default")
      (node (ref "D13") (pin "1") (pinfunction "C_1") (pintype "passive"))
      (node (ref "X14") (pin "1") (pinfunction "S_1") (pintype "passive"))
    )
    (net (code "44") (name "Net-(D14-A)") (class "Default")
      (node (ref "D14") (pin "2") (pinfunction "A_2") (pintype "passive"))
      (node (ref "D30") (pin "2") (pinfunction "A_2") (pintype "passive"))
      (node (ref "D38") (pin "2") (pinfunction "A_2") (pintype "passive"))
      (node (ref "D69") (pin "2") (pinfunction "A_2") (pintype "passive"))
      (node (ref "D7") (pin "2") (pinfunction "A_2") (pintype "passive"))
      (node (ref "D76") (pin "2") (pinfunction "A_2") (pintype "passive"))
      (node (ref "D84") (pin "2") (pinfunction "A_2") (pintype "passive"))
      (node (ref "D92") (pin "2") (pinfunction "A_2") (pintype "passive"))
      (node (ref "Q7") (pin "3") (pinfunction "D_3") (pintype "passive"))
    )
    (net (code "45") (name "Net-(D14-C)") (class "Default")
      (node (ref "D14") (pin "1") (pinfunction "C_1") (pintype "passive"))
      (node (ref "X15") (pin "1") (pinfunction "S_1") (pintype "passive"))
    )
    (net (code "46") (name "Net-(D15-A)") (class "Default")
      (node (ref "D15") (pin "2") (pinfunction "A_2") (pintype "passive"))
      (node (ref "D31") (pin "2") (pinfunction "A_2") (pintype "passive"))
      (node (ref "D39") (pin "2") (pinfunction "A_2") (pintype "passive"))
      (node (ref "D70") (pin "2") (pinfunction "A_2") (pintype "passive"))
      (node (ref "D77") (pin "2") (pinfunction "A_2") (pintype "passive"))
      (node (ref "D8") (pin "2") (pinfunction "A_2") (pintype "passive"))
      (node (ref "D85") (pin "2") (pinfunction "A_2") (pintype "passive"))
      (node (ref "D93") (pin "2") (pinfunction "A_2") (pintype "passive"))
      (node (ref "Q8") (pin "3") (pinfunction "D_3") (pintype "passive"))
    )
    (net (code "47") (name "Net-(D15-C)") (class "Default")
      (node (ref "D15") (pin "1") (pinfunction "C_1") (pintype "passive"))
      (node (ref "X16") (pin "1") (pinfunction "S_1") (pintype "passive"))
    )
    (net (code "48") (name "Net-(D17-C)") (class "Default")
      (node (ref "D17") (pin "1") (pinfunction "C_1") (pintype "passive"))
      (node (ref "X9") (pin "1") (pinfunction "S_1") (pintype "passive"))
    )
    (net (code "49") (name "Net-(D22-C)") (class "Default")
      (node (ref "D22") (pin "1") (pinfunction "C_1") (pintype "passive"))
      (node (ref "X46") (pin "1") (pinfunction "S_1") (pintype "passive"))
    )
    (net (code "50") (name "Net-(D24-C)") (class "Default")
      (node (ref "D24") (pin "1") (pinfunction "C_1") (pintype "passive"))
      (node (ref "X17") (pin "1") (pinfunction "S_1") (pintype "passive"))
    )
    (net (code "51") (name "Net-(D25-C)") (class "Default")
      (node (ref "D25") (pin "1") (pinfunction "C_1") (pintype "passive"))
      (node (ref "X18") (pin "1") (pinfunction "S_1") (pintype "passive"))
    )
    (net (code "52") (name "Net-(D26-C)") (class "Default")
      (node (ref "D26") (pin "1") (pinfunction "C_1") (pintype "passive"))
      (node (ref "X19") (pin "1") (pinfunction "S_1") (pintype "passive"))
    )
    (net (code "53") (name "Net-(D27-C)") (class "Default")
      (node (ref "D27") (pin "1") (pinfunction "C_1") (pintype "passive"))
      (node (ref "X20") (pin "1") (pinfunction "S_1") (pintype "passive"))
    )
    (net (code "54") (name "Net-(D28-C)") (class "Default")
      (node (ref "D28") (pin "1") (pinfunction "C_1") (pintype "passive"))
      (node (ref "X21") (pin "1") (pinfunction "S_1") (pintype "passive"))
    )
    (net (code "55") (name "Net-(D29-C)") (class "Default")
      (node (ref "D29") (pin "1") (pinfunction "C_1") (pintype "passive"))
      (node (ref "X22") (pin "1") (pinfunction "S_1") (pintype "passive"))
    )
    (net (code "56") (name "Net-(D30-C)") (class "Default")
      (node (ref "D30") (pin "1") (pinfunction "C_1") (pintype "passive"))
      (node (ref "X23") (pin "1") (pinfunction "S_1") (pintype "passive"))
    )
    (net (code "57") (name "Net-(D31-C)") (class "Default")
      (node (ref "D31") (pin "1") (pinfunction "C_1") (pintype "passive"))
      (node (ref "X24") (pin "1") (pinfunction "S_1") (pintype "passive"))
    )
    (net (code "58") (name "Net-(D32-C)") (class "Default")
      (node (ref "D32") (pin "1") (pinfunction "C_1") (pintype "passive"))
      (node (ref "X25") (pin "1") (pinfunction "S_1") (pintype "passive"))
    )
    (net (code "59") (name "Net-(D33-C)") (class "Default")
      (node (ref "D33") (pin "1") (pinfunction "C_1") (pintype "passive"))
      (node (ref "X26") (pin "1") (pinfunction "S_1") (pintype "passive"))
    )
    (net (code "60") (name "Net-(D34-C)") (class "Default")
      (node (ref "D34") (pin "1") (pinfunction "C_1") (pintype "passive"))
      (node (ref "X27") (pin "1") (pinfunction "S_1") (pintype "passive"))
    )
    (net (code "61") (name "Net-(D35-C)") (class "Default")
      (node (ref "D35") (pin "1") (pinfunction "C_1") (pintype "passive"))
      (node (ref "X28") (pin "1") (pinfunction "S_1") (pintype "passive"))
    )
    (net (code "62") (name "Net-(D36-C)") (class "Default")
      (node (ref "D36") (pin "1") (pinfunction "C_1") (pintype "passive"))
      (node (ref "X29") (pin "1") (pinfunction "S_1") (pintype "passive"))
    )
    (net (code "63") (name "Net-(D37-C)") (class "Default")
      (node (ref "D37") (pin "1") (pinfunction "C_1") (pintype "passive"))
      (node (ref "X30") (pin "1") (pinfunction "S_1") (pintype "passive"))
    )
    (net (code "64") (name "Net-(D38-C)") (class "Default")
      (node (ref "D38") (pin "1") (pinfunction "C_1") (pintype "passive"))
      (node (ref "X31") (pin "1") (pinfunction "S_1") (pintype "passive"))
    )
    (net (code "65") (name "Net-(D39-C)") (class "Default")
      (node (ref "D39") (pin "1") (pinfunction "C_1") (pintype "passive"))
      (node (ref "X32") (pin "1") (pinfunction "S_1") (pintype "passive"))
    )
    (net (code "66") (name "Net-(D63-C)") (class "Default")
      (node (ref "D63") (pin "1") (pinfunction "C_1") (pintype "passive"))
      (node (ref "X33") (pin "1") (pinfunction "S_1") (pintype "passive"))
    )
    (net (code "67") (name "Net-(D64-C)") (class "Default")
      (node (ref "D64") (pin "1") (pinfunction "C_1") (pintype "passive"))
      (node (ref "X34") (pin "1") (pinfunction "S_1") (pintype "passive"))
    )
    (net (code "68") (name "Net-(D65-C)") (class "Default")
      (node (ref "D65") (pin "1") (pinfunction "C_1") (pintype "passive"))
      (node (ref "X35") (pin "1") (pinfunction "S_1") (pintype "passive"))
    )
    (net (code "69") (name "Net-(D66-C)") (class "Default")
      (node (ref "D66") (pin "1") (pinfunction "C_1") (pintype "passive"))
      (node (ref "X36") (pin "1") (pinfunction "S_1") (pintype "passive"))
    )
    (net (code "70") (name "Net-(D67-C)") (class "Default")
      (node (ref "D67") (pin "1") (pinfunction "C_1") (pintype "passive"))
      (node (ref "X37") (pin "1") (pinfunction "S_1") (pintype "passive"))
    )
    (net (code "71") (name "Net-(D68-C)") (class "Default")
      (node (ref "D68") (pin "1") (pinfunction "C_1") (pintype "passive"))
      (node (ref "X38") (pin "1") (pinfunction "S_1") (pintype "passive"))
    )
    (net (code "72") (name "Net-(D69-C)") (class "Default")
      (node (ref "D69") (pin "1") (pinfunction "C_1") (pintype "passive"))
      (node (ref "X39") (pin "1") (pinfunction "S_1") (pintype "passive"))
    )
    (net (code "73") (name "Net-(D70-C)") (class "Default")
      (node (ref "D70") (pin "1") (pinfunction "C_1") (pintype "passive"))
      (node (ref "X40") (pin "1") (pinfunction "S_1") (pintype "passive"))
    )
    (net (code "74") (name "Net-(D71-C)") (class "Default")
      (node (ref "D71") (pin "1") (pinfunction "C_1") (pintype "passive"))
      (node (ref "X41") (pin "1") (pinfunction "S_1") (pintype "passive"))
    )
    (net (code "75") (name "Net-(D72-C)") (class "Default")
      (node (ref "D72") (pin "1") (pinfunction "C_1") (pintype "passive"))
      (node (ref "X42") (pin "1") (pinfunction "S_1") (pintype "passive"))
    )
    (net (code "76") (name "Net-(D73-C)") (class "Default")
      (node (ref "D73") (pin "1") (pinfunction "C_1") (pintype "passive"))
      (node (ref "X43") (pin "1") (pinfunction "S_1") (pintype "passive"))
    )
    (net (code "77") (name "Net-(D74-C)") (class "Default")
      (node (ref "D74") (pin "1") (pinfunction "C_1") (pintype "passive"))
      (node (ref "X44") (pin "1") (pinfunction "S_1") (pintype "passive"))
    )
    (net (code "78") (name "Net-(D75-C)") (class "Default")
      (node (ref "D75") (pin "1") (pinfunction "C_1") (pintype "passive"))
      (node (ref "X45") (pin "1") (pinfunction "S_1") (pintype "passive"))
    )
    (net (code "79") (name "Net-(D76-C)") (class "Default")
      (node (ref "D76") (pin "1") (pinfunction "C_1") (pintype "passive"))
      (node (ref "X47") (pin "1") (pinfunction "S_1") (pintype "passive"))
    )
    (net (code "80") (name "Net-(D77-C)") (class "Default")
      (node (ref "D77") (pin "1") (pinfunction "C_1") (pintype "passive"))
      (node (ref "X48") (pin "1") (pinfunction "S_1") (pintype "passive"))
    )
    (net (code "81") (name "Net-(D78-C)") (class "Default")
      (node (ref "D78") (pin "1") (pinfunction "C_1") (pintype "passive"))
      (node (ref "X49") (pin "1") (pinfunction "S_1") (pintype "passive"))
    )
    (net (code "82") (name "Net-(D79-C)") (class "Default")
      (node (ref "D79") (pin "1") (pinfunction "C_1") (pintype "passive"))
      (node (ref "X50") (pin "1") (pinfunction "S_1") (pintype "passive"))
    )
    (net (code "83") (name "Net-(D80-C)") (class "Default")
      (node (ref "D80") (pin "1") (pinfunction "C_1") (pintype "passive"))
      (node (ref "X51") (pin "1") (pinfunction "S_1") (pintype "passive"))
    )
    (net (code "84") (name "Net-(D81-C)") (class "Default")
      (node (ref "D81") (pin "1") (pinfunction "C_1") (pintype "passive"))
      (node (ref "X52") (pin "1") (pinfunction "S_1") (pintype "passive"))
    )
    (net (code "85") (name "Net-(D82-C)") (class "Default")
      (node (ref "D82") (pin "1") (pinfunction "C_1") (pintype "passive"))
      (node (ref "X53") (pin "1") (pinfunction "S_1") (pintype "passive"))
    )
    (net (code "86") (name "Net-(D83-C)") (class "Default")
      (node (ref "D83") (pin "1") (pinfunction "C_1") (pintype "passive"))
      (node (ref "X54") (pin "1") (pinfunction "S_1") (pintype "passive"))
    )
    (net (code "87") (name "Net-(D84-C)") (class "Default")
      (node (ref "D84") (pin "1") (pinfunction "C_1") (pintype "passive"))
      (node (ref "X55") (pin "1") (pinfunction "S_1") (pintype "passive"))
    )
    (net (code "88") (name "Net-(D85-C)") (class "Default")
      (node (ref "D85") (pin "1") (pinfunction "C_1") (pintype "passive"))
      (node (ref "X56") (pin "1") (pinfunction "S_1") (pintype "passive"))
    )
    (net (code "89") (name "Net-(D86-C)") (class "Default")
      (node (ref "D86") (pin "1") (pinfunction "C_1") (pintype "passive"))
      (node (ref "X57") (pin "1") (pinfunction "S_1") (pintype "passive"))
    )
    (net (code "90") (name "Net-(D87-C)") (class "Default")
      (node (ref "D87") (pin "1") (pinfunction "C_1") (pintype "passive"))
      (node (ref "X58") (pin "1") (pinfunction "S_1") (pintype "passive"))
    )
    (net (code "91") (name "Net-(D88-C)") (class "Default")
      (node (ref "D88") (pin "1") (pinfunction "C_1") (pintype "passive"))
      (node (ref "X59") (pin "1") (pinfunction "S_1") (pintype "passive"))
    )
    (net (code "92") (name "Net-(D89-C)") (class "Default")
      (node (ref "D89") (pin "1") (pinfunction "C_1") (pintype "passive"))
      (node (ref "X60") (pin "1") (pinfunction "S_1") (pintype "passive"))
    )
    (net (code "93") (name "Net-(D90-C)") (class "Default")
      (node (ref "D90") (pin "1") (pinfunction "C_1") (pintype "passive"))
      (node (ref "X61") (pin "1") (pinfunction "S_1") (pintype "passive"))
    )
    (net (code "94") (name "Net-(D91-C)") (class "Default")
      (node (ref "D91") (pin "1") (pinfunction "C_1") (pintype "passive"))
      (node (ref "X62") (pin "1") (pinfunction "S_1") (pintype "passive"))
    )
    (net (code "95") (name "Net-(D92-C)") (class "Default")
      (node (ref "D92") (pin "1") (pinfunction "C_1") (pintype "passive"))
      (node (ref "X63") (pin "1") (pinfunction "S_1") (pintype "passive"))
    )
    (net (code "96") (name "Net-(D93-C)") (class "Default")
      (node (ref "D93") (pin "1") (pinfunction "C_1") (pintype "passive"))
      (node (ref "X64") (pin "1") (pinfunction "S_1") (pintype "passive"))
    )
    (net (code "97") (name "Net-(Q1-G)") (class "Default")
      (node (ref "Q1") (pin "1") (pinfunction "G_1") (pintype "passive"))
      (node (ref "R2") (pin "1") (pinfunction "1_1") (pintype "passive"))
      (node (ref "T1") (pin "3") (pinfunction "C_3") (pintype "passive"))
    )
    (net (code "98") (name "Net-(Q2-G)") (class "Default")
      (node (ref "Q2") (pin "1") (pinfunction "G_1") (pintype "passive"))
      (node (ref "R4") (pin "1") (pinfunction "1_1") (pintype "passive"))
      (node (ref "T2") (pin "3") (pinfunction "C_3") (pintype "passive"))
    )
    (net (code "99") (name "Net-(Q3-G)") (class "Default")
      (node (ref "Q3") (pin "1") (pinfunction "G_1") (pintype "passive"))
      (node (ref "R8") (pin "1") (pinfunction "1_1") (pintype "passive"))
      (node (ref "T4") (pin "3") (pinfunction "C_3") (pintype "passive"))
    )
    (net (code "100") (name "Net-(Q4-G)") (class "Default")
      (node (ref "Q4") (pin "1") (pinfunction "G_1") (pintype "passive"))
      (node (ref "R10") (pin "1") (pinfunction "1_1") (pintype "passive"))
      (node (ref "T5") (pin "3") (pinfunction "C_3") (pintype "passive"))
    )
    (net (code "101") (name "Net-(Q5-G)") (class "Default")
      (node (ref "Q5") (pin "1") (pinfunction "G_1") (pintype "passive"))
      (node (ref "R12") (pin "1") (pinfunction "1_1") (pintype "passive"))
      (node (ref "T6") (pin "3") (pinfunction "C_3") (pintype "passive"))
    )
    (net (code "102") (name "Net-(Q6-G)") (class "Default")
      (node (ref "Q6") (pin "1") (pinfunction "G_1") (pintype "passive"))
      (node (ref "R14") (pin "1") (pinfunction "1_1") (pintype "passive"))
      (node (ref "T7") (pin "3") (pinfunction "C_3") (pintype "passive"))
    )
    (net (code "103") (name "Net-(Q7-G)") (class "Default")
      (node (ref "Q7") (pin "1") (pinfunction "G_1") (pintype "passive"))
      (node (ref "R16") (pin "1") (pinfunction "1_1") (pintype "passive"))
      (node (ref "T8") (pin "3") (pinfunction "C_3") (pintype "passive"))
    )
    (net (code "104") (name "Net-(Q8-G)") (class "Default")
      (node (ref "Q8") (pin "1") (pinfunction "G_1") (pintype "passive"))
      (node (ref "R18") (pin "1") (pinfunction "1_1") (pintype "passive"))
      (node (ref "T9") (pin "3") (pinfunction "C_3") (pintype "passive"))
    )
    (net (code "105") (name "Net-(Q10-D)") (class "Default")
      (node (ref "Q10") (pin "3") (pinfunction "D_3") (pintype "passive"))
      (node (ref "X1") (pin "2") (pinfunction "S_2") (pintype "passive"))
      (node (ref "X2") (pin "2") (pinfunction "S_2") (pintype "passive"))
      (node (ref "X3") (pin "2") (pinfunction "S_2") (pintype "passive"))
      (node (ref "X4") (pin "2") (pinfunction "S_2") (pintype "passive"))
      (node (ref "X5") (pin "2") (pinfunction "S_2") (pintype "passive"))
      (node (ref "X6") (pin "2") (pinfunction "S_2") (pintype "passive"))
      (node (ref "X7") (pin "2") (pinfunction "S_2") (pintype "passive"))
      (node (ref "X8") (pin "2") (pinfunction "S_2") (pintype "passive"))
    )
    (net (code "106") (name "Net-(Q10-G)") (class "Default")
      (node (ref "Q10") (pin "1") (pinfunction "G_1") (pintype "passive"))
      (node (ref "R19") (pin "1") (pinfunction "1_1") (pintype "passive"))
    )
    (net (code "107") (name "Net-(Q11-D)") (class "Default")
      (node (ref "Q11") (pin "3") (pinfunction "D_3") (pintype "passive"))
      (node (ref "X10") (pin "2") (pinfunction "S_2") (pintype "passive"))
      (node (ref "X11") (pin "2") (pinfunction "S_2") (pintype "passive"))
      (node (ref "X12") (pin "2") (pinfunction "S_2") (pintype "passive"))
      (node (ref "X13") (pin "2") (pinfunction "S_2") (pintype "passive"))
      (node (ref "X14") (pin "2") (pinfunction "S_2") (pintype "passive"))
      (node (ref "X15") (pin "2") (pinfunction "S_2") (pintype "passive"))
      (node (ref "X16") (pin "2") (pinfunction "S_2") (pintype "passive"))
      (node (ref "X9") (pin "2") (pinfunction "S_2") (pintype "passive"))
    )
    (net (code "108") (name "Net-(Q11-G)") (class "Default")
      (node (ref "Q11") (pin "1") (pinfunction "G_1") (pintype "passive"))
      (node (ref "R21") (pin "1") (pinfunction "1_1") (pintype "passive"))
    )
    (net (code "109") (name "Net-(Q12-D)") (class "Default")
      (node (ref "Q12") (pin "3") (pinfunction "D_3") (pintype "passive"))
      (node (ref "X17") (pin "2") (pinfunction "S_2") (pintype "passive"))
      (node (ref "X18") (pin "2") (pinfunction "S_2") (pintype "passive"))
      (node (ref "X19") (pin "2") (pinfunction "S_2") (pintype "passive"))
      (node (ref "X20") (pin "2") (pinfunction "S_2") (pintype "passive"))
      (node (ref "X21") (pin "2") (pinfunction "S_2") (pintype "passive"))
      (node (ref "X22") (pin "2") (pinfunction "S_2") (pintype "passive"))
      (node (ref "X23") (pin "2") (pinfunction "S_2") (pintype "passive"))
      (node (ref "X24") (pin "2") (pinfunction "S_2") (pintype "passive"))
    )
    (net (code "110") (name "Net-(Q12-G)") (class "Default")
      (node (ref "Q12") (pin "1") (pinfunction "G_1") (pintype "passive"))
      (node (ref "R23") (pin "1") (pinfunction "1_1") (pintype "passive"))
    )
    (net (code "111") (name "Net-(Q13-D)") (class "Default")
      (node (ref "Q13") (pin "3") (pinfunction "D_3") (pintype "passive"))
      (node (ref "X25") (pin "2") (pinfunction "S_2") (pintype "passive"))
      (node (ref "X26") (pin "2") (pinfunction "S_2") (pintype "passive"))
      (node (ref "X27") (pin "2") (pinfunction "S_2") (pintype "passive"))
      (node (ref "X28") (pin "2") (pinfunction "S_2") (pintype "passive"))
      (node (ref "X29") (pin "2") (pinfunction "S_2") (pintype "passive"))
      (node (ref "X30") (pin "2") (pinfunction "S_2") (pintype "passive"))
      (node (ref "X31") (pin "2") (pinfunction "S_2") (pintype "passive"))
      (node (ref "X32") (pin "2") (pinfunction "S_2") (pintype "passive"))
    )
    (net (code "112") (name "Net-(Q13-G)") (class "Default")
      (node (ref "Q13") (pin "1") (pinfunction "G_1") (pintype "passive"))
      (node (ref "R25") (pin "1") (pinfunction "1_1") (pintype "passive"))
    )
    (net (code "113") (name "Net-(Q17-D)") (class "Default")
      (node (ref "Q17") (pin "3") (pinfunction "D_3") (pintype "passive"))
      (node (ref "X33") (pin "2") (pinfunction "S_2") (pintype "passive"))
      (node (ref "X34") (pin "2") (pinfunction "S_2") (pintype "passive"))
      (node (ref "X35") (pin "2") (pinfunction "S_2") (pintype "passive"))
      (node (ref "X36") (pin "2") (pinfunction "S_2") (pintype "passive"))
      (node (ref "X37") (pin "2") (pinfunction "S_2") (pintype "passive"))
      (node (ref "X38") (pin "2") (pinfunction "S_2") (pintype "passive"))
      (node (ref "X39") (pin "2") (pinfunction "S_2") (pintype "passive"))
      (node (ref "X40") (pin "2") (pinfunction "S_2") (pintype "passive"))
    )
    (net (code "114") (name "Net-(Q17-G)") (class "Default")
      (node (ref "Q17") (pin "1") (pinfunction "G_1") (pintype "passive"))
      (node (ref "R33") (pin "1") (pinfunction "1_1") (pintype "passive"))
    )
    (net (code "115") (name "Net-(Q18-D)") (class "Default")
      (node (ref "Q18") (pin "3") (pinfunction "D_3") (pintype "passive"))
      (node (ref "X41") (pin "2") (pinfunction "S_2") (pintype "passive"))
      (node (ref "X42") (pin "2") (pinfunction "S_2") (pintype "passive"))
      (node (ref "X43") (pin "2") (pinfunction "S_2") (pintype "passive"))
      (node (ref "X44") (pin "2") (pinfunction "S_2") (pintype "passive"))
      (node (ref "X45") (pin "2") (pinfunction "S_2") (pintype "passive"))
      (node (ref "X46") (pin "2") (pinfunction "S_2") (pintype "passive"))
      (node (ref "X47") (pin "2") (pinfunction "S_2") (pintype "passive"))
      (node (ref "X48") (pin "2") (pinfunction "S_2") (pintype "passive"))
    )
    (net (code "116") (name "Net-(Q18-G)") (class "Default")
      (node (ref "Q18") (pin "1") (pinfunction "G_1") (pintype "passive"))
      (node (ref "R35") (pin "1") (pinfunction "1_1") (pintype "passive"))
    )
    (net (code "117") (name "Net-(Q19-D)") (class "Default")
      (node (ref "Q19") (pin "3") (pinfunction "D_3") (pintype "passive"))
      (node (ref "X49") (pin "2") (pinfunction "S_2") (pintype "passive"))
      (node (ref "X50") (pin "2") (pinfunction "S_2") (pintype "passive"))
      (node (ref "X51") (pin "2") (pinfunction "S_2") (pintype "passive"))
      (node (ref "X52") (pin "2") (pinfunction "S_2") (pintype "passive"))
      (node (ref "X53") (pin "2") (pinfunction "S_2") (pintype "passive"))
      (node (ref "X54") (pin "2") (pinfunction "S_2") (pintype "passive"))
      (node (ref "X55") (pin "2") (pinfunction "S_2") (pintype "passive"))
      (node (ref "X56") (pin "2") (pinfunction "S_2") (pintype "passive"))
    )
    (net (code "118") (name "Net-(Q19-G)") (class "Default")
      (node (ref "Q19") (pin "1") (pinfunction "G_1") (pintype "passive"))
      (node (ref "R37") (pin "1") (pinfunction "1_1") (pintype "passive"))
    )
    (net (code "119") (name "Net-(Q20-D)") (class "Default")
      (node (ref "Q20") (pin "3") (pinfunction "D_3") (pintype "passive"))
      (node (ref "X57") (pin "2") (pinfunction "S_2") (pintype "passive"))
      (node (ref "X58") (pin "2") (pinfunction "S_2") (pintype "passive"))
      (node (ref "X59") (pin "2") (pinfunction "S_2") (pintype "passive"))
      (node (ref "X60") (pin "2") (pinfunction "S_2") (pintype "passive"))
      (node (ref "X61") (pin "2") (pinfunction "S_2") (pintype "passive"))
      (node (ref "X62") (pin "2") (pinfunction "S_2") (pintype "passive"))
      (node (ref "X63") (pin "2") (pinfunction "S_2") (pintype "passive"))
      (node (ref "X64") (pin "2") (pinfunction "S_2") (pintype "passive"))
    )
    (net (code "120") (name "Net-(Q20-G)") (class "Default")
      (node (ref "Q20") (pin "1") (pinfunction "G_1") (pintype "passive"))
      (node (ref "R39") (pin "1") (pinfunction "1_1") (pintype "passive"))
    )
    (net (code "121") (name "Net-(T1-B)") (class "Default")
      (node (ref "R1") (pin "2") (pinfunction "2_2") (pintype "passive"))
      (node (ref "T1") (pin "1") (pinfunction "B_1") (pintype "passive"))
    )
    (net (code "122") (name "Net-(T2-B)") (class "Default")
      (node (ref "R3") (pin "2") (pinfunction "2_2") (pintype "passive"))
      (node (ref "T2") (pin "1") (pinfunction "B_1") (pintype "passive"))
    )
    (net (code "123") (name "Net-(T4-B)") (class "Default")
      (node (ref "R7") (pin "2") (pinfunction "2_2") (pintype "passive"))
      (node (ref "T4") (pin "1") (pinfunction "B_1") (pintype "passive"))
    )
    (net (code "124") (name "Net-(T5-B)") (class "Default")
      (node (ref "R9") (pin "2") (pinfunction "2_2") (pintype "passive"))
      (node (ref "T5") (pin "1") (pinfunction "B_1") (pintype "passive"))
    )
    (net (code "125") (name "Net-(T6-B)") (class "Default")
      (node (ref "R11") (pin "2") (pinfunction "2_2") (pintype "passive"))
      (node (ref "T6") (pin "1") (pinfunction "B_1") (pintype "passive"))
    )
    (net (code "126") (name "Net-(T7-B)") (class "Default")
      (node (ref "R13") (pin "2") (pinfunction "2_2") (pintype "passive"))
      (node (ref "T7") (pin "1") (pinfunction "B_1") (pintype "passive"))
    )
    (net (code "127") (name "Net-(T8-B)") (class "Default")
      (node (ref "R15") (pin "2") (pinfunction "2_2") (pintype "passive"))
      (node (ref "T8") (pin "1") (pinfunction "B_1") (pintype "passive"))
    )
    (net (code "128") (name "Net-(T9-B)") (class "Default")
      (node (ref "R17") (pin "2") (pinfunction "2_2") (pintype "passive"))
      (node (ref "T9") (pin "1") (pinfunction "B_1") (pintype "passive"))
    )
    (net (code "129") (name "unconnected-(U2-INT-Pad1)") (class "Default")
      (node (ref "U2") (pin "1") (pinfunction "INT_1") (pintype "output"))
    )
  )
)
